# tms9918.net
KiCad netlist of a schematic drawn in EAGLE
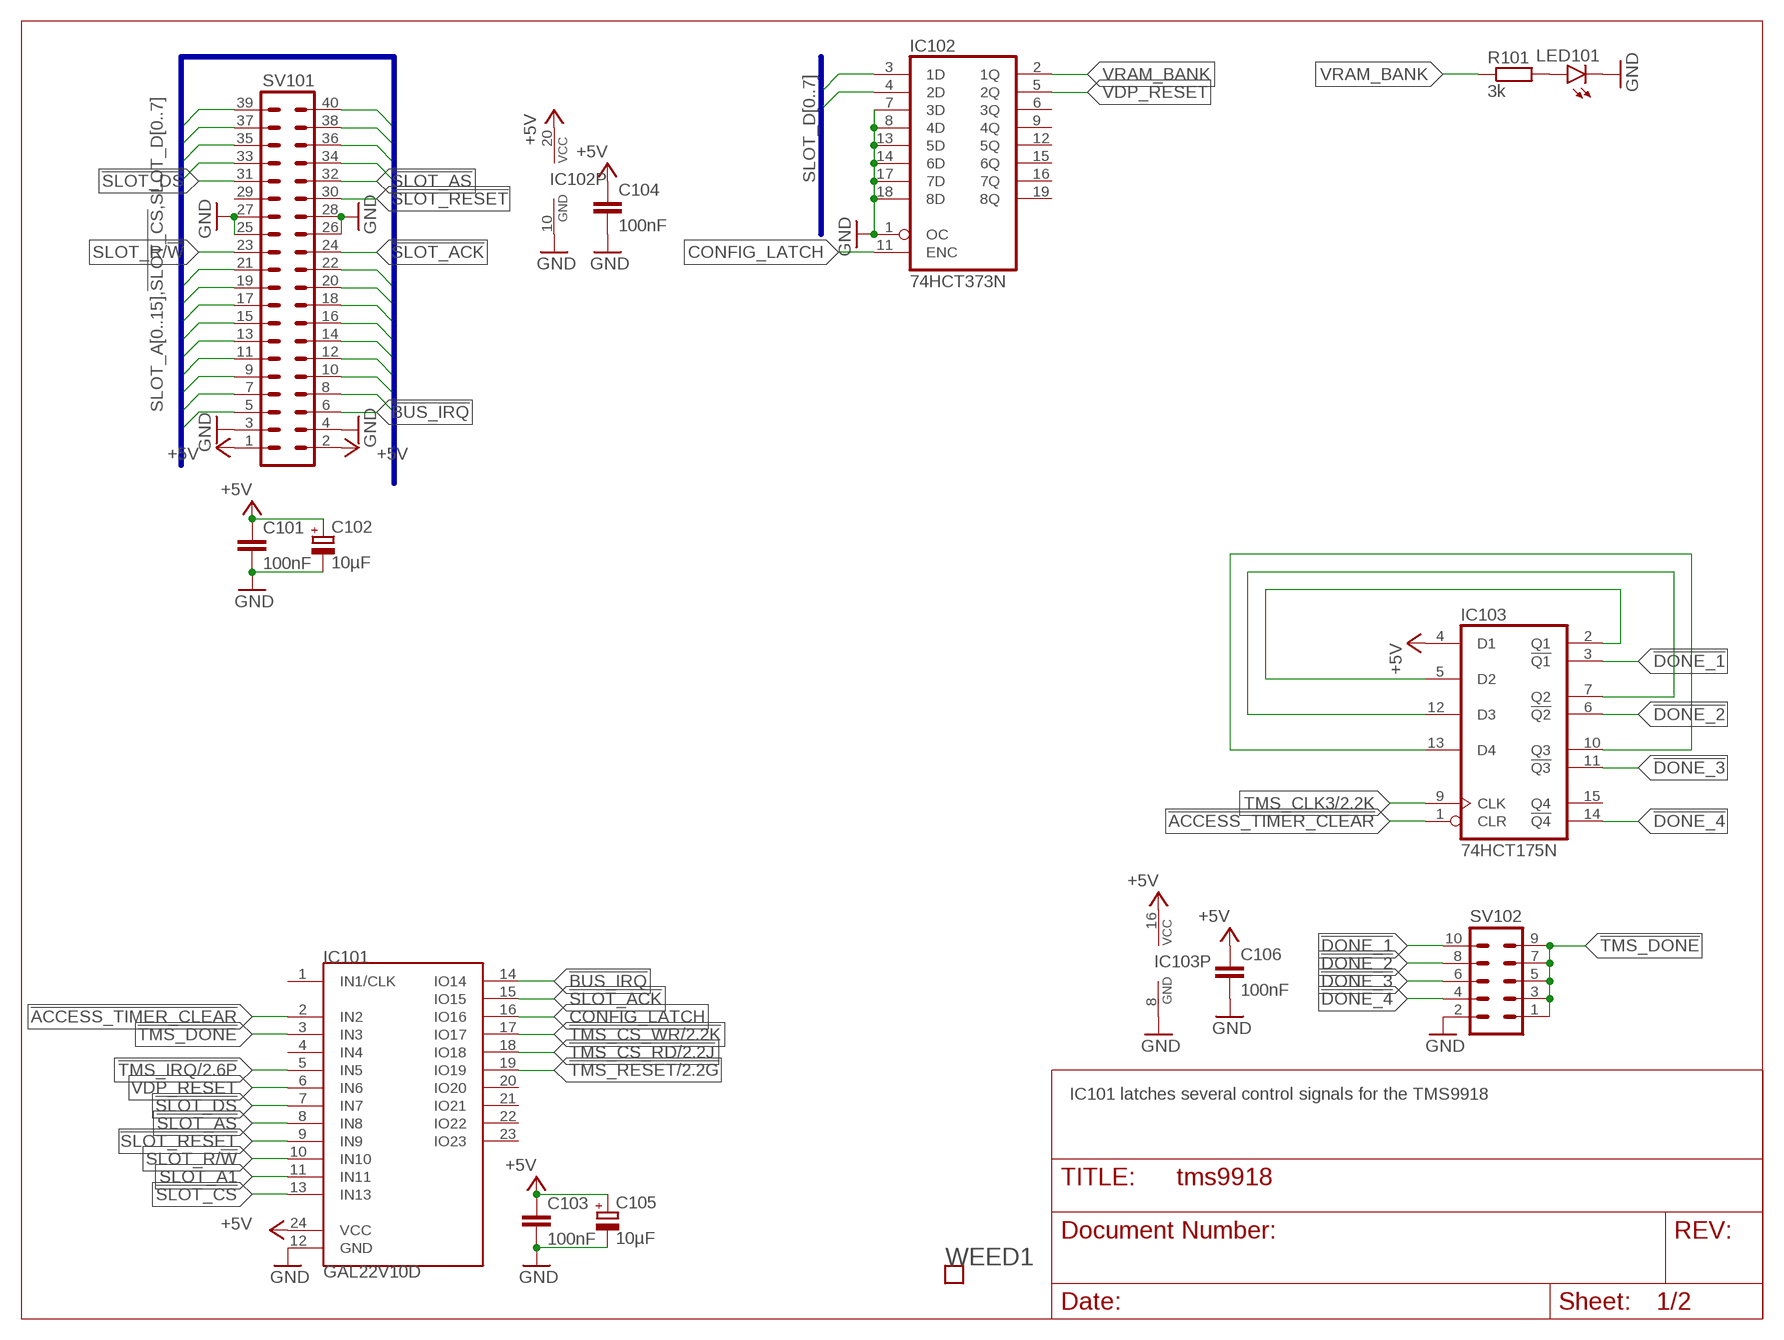
[diagram p0: schematic, sheet 1]
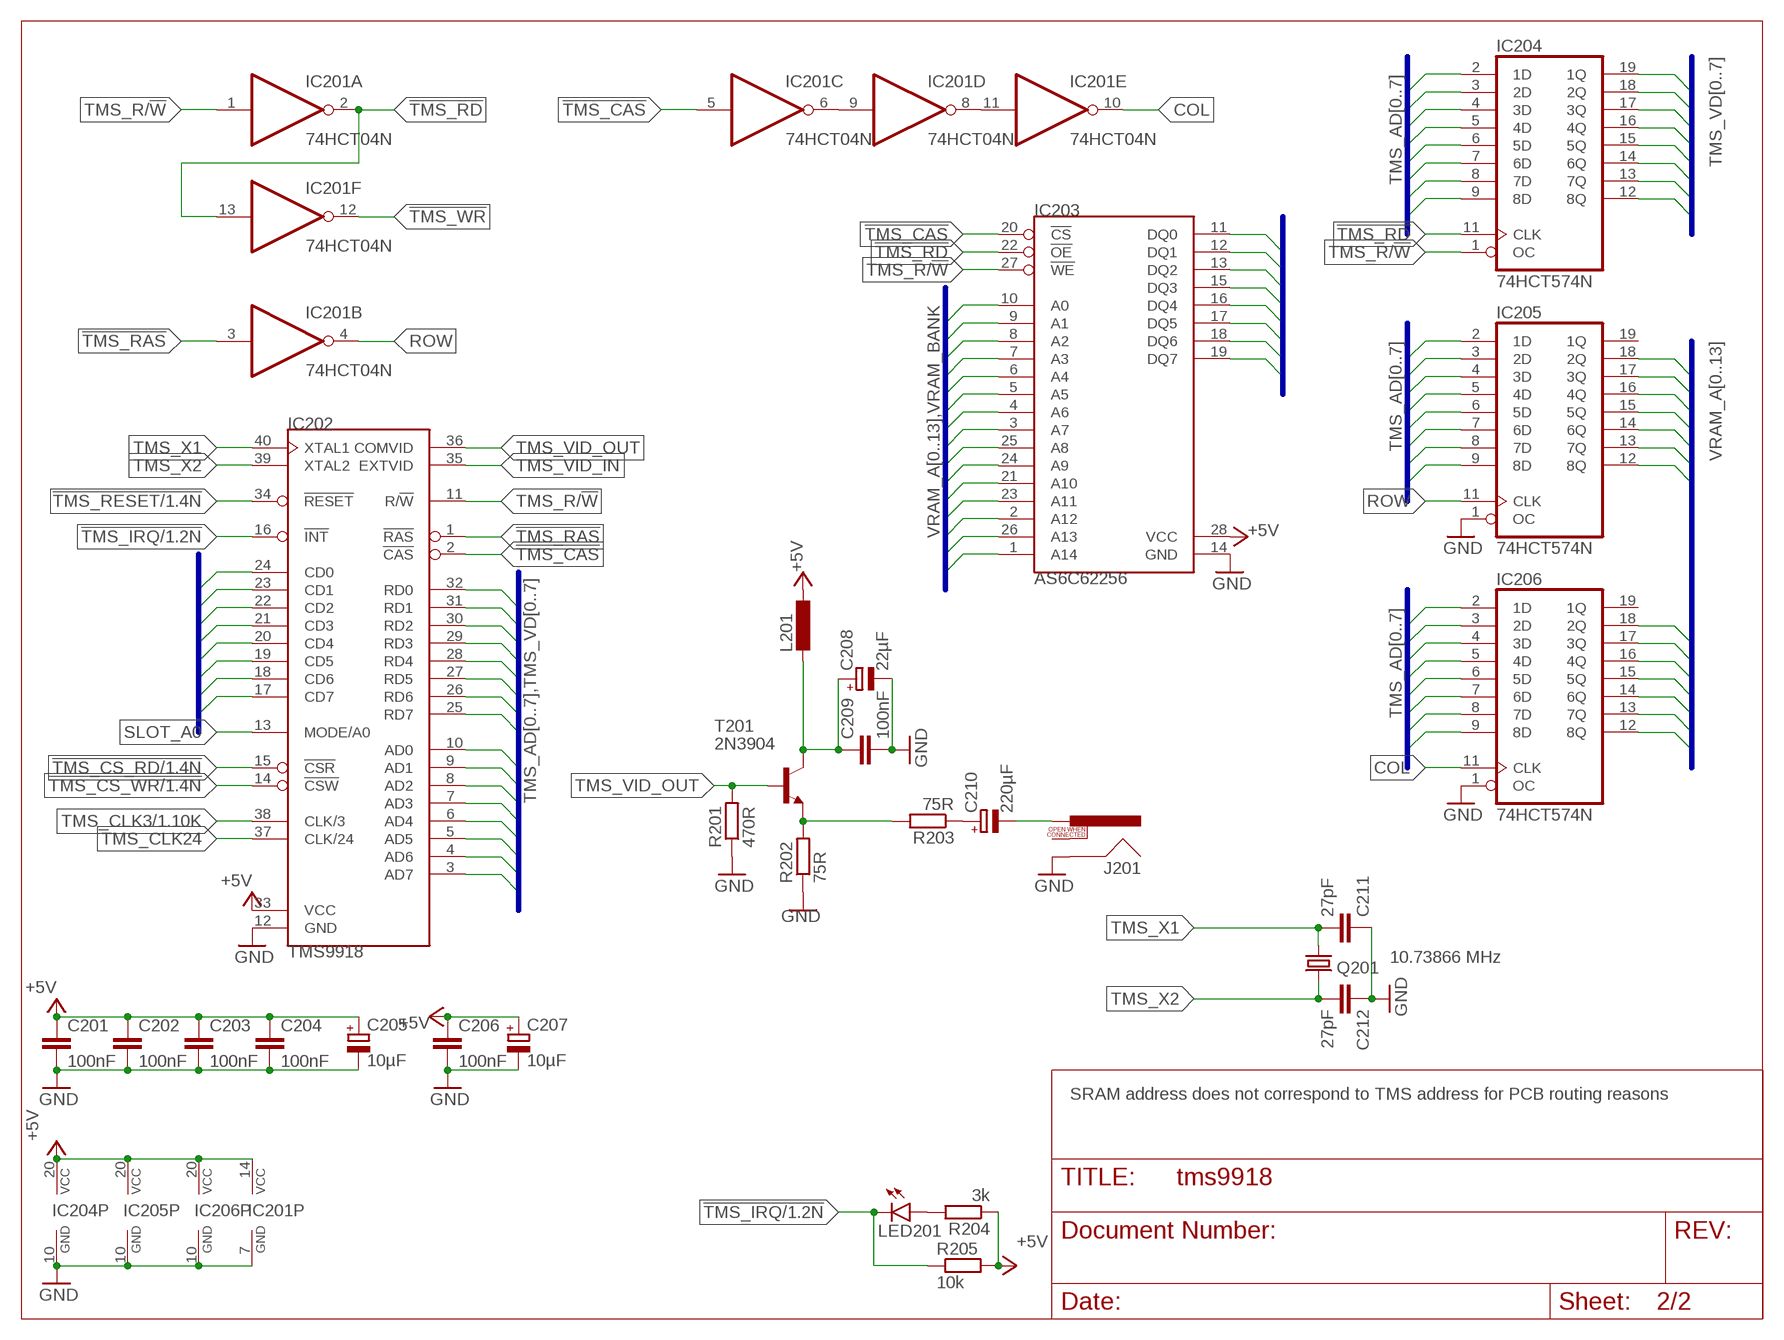
[diagram p1: schematic, sheet 2]

(export (version "E")
  (design (tool "Eeschema 10.0.6"))
  (components
    (comp (ref "C201")
      (value "100nF")
      (footprint "eagle-import:C0805")
      (libsource (lib "eagle-import") (part "C-EUC0805"))
    )
    (comp (ref "C202")
      (value "100nF")
      (footprint "eagle-import:C0805")
      (libsource (lib "eagle-import") (part "C-EUC0805"))
    )
    (comp (ref "C203")
      (value "100nF")
      (footprint "eagle-import:C0805")
      (libsource (lib "eagle-import") (part "C-EUC0805"))
    )
    (comp (ref "C204")
      (value "100nF")
      (footprint "eagle-import:C0805")
      (libsource (lib "eagle-import") (part "C-EUC0805"))
    )
    (comp (ref "C205")
      (value "10µF")
      (footprint "eagle-import:SMC_B")
      (libsource (lib "eagle-import") (part "CPOL-EUSMCB"))
    )
    (comp (ref "C206")
      (value "100nF")
      (footprint "eagle-import:C0805")
      (libsource (lib "eagle-import") (part "C-EUC0805"))
    )
    (comp (ref "C207")
      (value "10µF")
      (footprint "eagle-import:SMC_B")
      (libsource (lib "eagle-import") (part "CPOL-EUSMCB"))
    )
    (comp (ref "C208")
      (value "22µF")
      (footprint "eagle-import:E2-5")
      (libsource (lib "eagle-import") (part "CPOL-EUE2-5"))
    )
    (comp (ref "C209")
      (value "100nF")
      (footprint "eagle-import:C0805")
      (libsource (lib "eagle-import") (part "C-EUC0805"))
    )
    (comp (ref "C210")
      (value "220µF")
      (footprint "eagle-import:E2,5-7")
      (libsource (lib "eagle-import") (part "CPOL-EUE2.5-7"))
    )
    (comp (ref "C211")
      (value "27pF")
      (footprint "eagle-import:C0805")
      (libsource (lib "eagle-import") (part "C-EUC0805"))
    )
    (comp (ref "C212")
      (value "27pF")
      (footprint "eagle-import:C0805")
      (libsource (lib "eagle-import") (part "C-EUC0805"))
    )
    (comp (ref "IC201")
      (value "74HCT04N")
      (footprint "eagle-import:DIL14")
      (fields (field (name "MOUSER") "595-SN74HCT04N") (field (name "MOUSER_SOCKET") "575-1104731441001000"))
      (libsource (lib "eagle-import") (part "7404NHCT"))
    )
    (comp (ref "IC202")
      (value "TMS9918")
      (footprint "eagle-import:DIL40")
      (libsource (lib "eagle-import") (part "TMS9918"))
    )
    (comp (ref "IC203")
      (value "AS6C62256")
      (footprint "eagle-import:DIL28-6")
      (libsource (lib "eagle-import") (part "AS6C62256"))
    )
    (comp (ref "IC204")
      (value "74HCT574N")
      (footprint "eagle-import:DIL20")
      (fields (field (name "MOUSER") "595-SN74HCT574N") (field (name "MOUSER_SOCKET") "575-1104732041001000"))
      (libsource (lib "eagle-import") (part "74574NHCT"))
    )
    (comp (ref "IC205")
      (value "74HCT574N")
      (footprint "eagle-import:DIL20")
      (fields (field (name "MOUSER") "595-SN74HCT574N") (field (name "MOUSER_SOCKET") "575-1104732041001000"))
      (libsource (lib "eagle-import") (part "74574NHCT"))
    )
    (comp (ref "IC206")
      (value "74HCT574N")
      (footprint "eagle-import:DIL20")
      (fields (field (name "MOUSER") "595-SN74HCT574N") (field (name "MOUSER_SOCKET") "575-1104732041001000"))
      (libsource (lib "eagle-import") (part "74574NHCT"))
    )
    (comp (ref "J201")
      (value "RCALOCK")
      (footprint "eagle-import:RCA_LOCK")
      (libsource (lib "eagle-import") (part "RCALOCK"))
    )
    (comp (ref "L201")
      (value "L-EUL2012C")
      (footprint "eagle-import:L2012C")
      (libsource (lib "eagle-import") (part "L-EUL2012C"))
    )
    (comp (ref "LED201")
      (value "LEDCHIPLED_1206")
      (footprint "eagle-import:CHIPLED_1206")
      (libsource (lib "eagle-import") (part "LEDCHIPLED_1206"))
    )
    (comp (ref "Q201")
      (value "10.73866 MHz")
      (footprint "eagle-import:HC49_S")
      (libsource (lib "eagle-import") (part "CRYSTALHC49S"))
    )
    (comp (ref "R201")
      (value "470R")
      (footprint "eagle-import:R2012")
      (libsource (lib "eagle-import") (part "R-EU_R2012"))
    )
    (comp (ref "R202")
      (value "75R")
      (footprint "eagle-import:R2012")
      (libsource (lib "eagle-import") (part "R-EU_R2012"))
    )
    (comp (ref "R203")
      (value "75R")
      (footprint "eagle-import:R2012")
      (libsource (lib "eagle-import") (part "R-EU_R2012"))
    )
    (comp (ref "R204")
      (value "3k")
      (footprint "eagle-import:R2012")
      (libsource (lib "eagle-import") (part "R-EU_R2012"))
    )
    (comp (ref "R205")
      (value "10k")
      (footprint "eagle-import:R2012")
      (libsource (lib "eagle-import") (part "R-EU_R2012"))
    )
    (comp (ref "T201")
      (value "2N3904")
      (footprint "eagle-import:TO92")
      (libsource (lib "eagle-import") (part "2N3904"))
    )
    (comp (ref "C101")
      (value "100nF")
      (footprint "eagle-import:C0805")
      (libsource (lib "eagle-import") (part "C-EUC0805"))
    )
    (comp (ref "C102")
      (value "10µF")
      (footprint "eagle-import:SMC_B")
      (libsource (lib "eagle-import") (part "CPOL-EUSMCB"))
    )
    (comp (ref "C103")
      (value "100nF")
      (footprint "eagle-import:C0805")
      (libsource (lib "eagle-import") (part "C-EUC0805"))
    )
    (comp (ref "C104")
      (value "100nF")
      (footprint "eagle-import:C0805")
      (libsource (lib "eagle-import") (part "C-EUC0805"))
    )
    (comp (ref "C105")
      (value "10µF")
      (footprint "eagle-import:SMC_B")
      (libsource (lib "eagle-import") (part "CPOL-EUSMCB"))
    )
    (comp (ref "C106")
      (value "100nF")
      (footprint "eagle-import:C0805")
      (libsource (lib "eagle-import") (part "C-EUC0805"))
    )
    (comp (ref "IC101")
      (value "GAL22V10D")
      (footprint "eagle-import:DIL24S")
      (libsource (lib "eagle-import") (part "GAL22V10DIP24"))
    )
    (comp (ref "IC102")
      (value "74HCT373N")
      (footprint "eagle-import:DIL20")
      (fields (field (name "MOUSER") "595-SN74HCT373N") (field (name "MOUSER_SOCKET") "575-1104732041001000"))
      (libsource (lib "eagle-import") (part "74373NHCT"))
    )
    (comp (ref "IC103")
      (value "74HCT175N")
      (footprint "eagle-import:DIL16")
      (fields (field (name "MOUSER") "595-CD74HCT175E") (field (name "MOUSER_SOCKET") "575-1104731641001000"))
      (libsource (lib "eagle-import") (part "74175NHCT"))
    )
    (comp (ref "LED101")
      (value "LEDCHIPLED_1206")
      (footprint "eagle-import:CHIPLED_1206")
      (libsource (lib "eagle-import") (part "LEDCHIPLED_1206"))
    )
    (comp (ref "R101")
      (value "3k")
      (footprint "eagle-import:R2012")
      (libsource (lib "eagle-import") (part "R-EU_R2012"))
    )
    (comp (ref "SV101")
      (value "MA20-2W")
      (footprint "eagle-import:MA20-2W")
      (libsource (lib "eagle-import") (part "MA20-2W"))
    )
    (comp (ref "SV102")
      (value "MA05-2")
      (footprint "eagle-import:MA05-2")
      (libsource (lib "eagle-import") (part "MA05-2"))
    )
    (comp (ref "WEED1")
      (value "WEED")
      (footprint "eagle-import:DOINK")
      (libsource (lib "eagle-import") (part "WEED"))
    )
  )
  (nets
    (net (code "1") (name "+5V") (class "Default")
      (node (ref "C101") (pin "1") (pinfunction "1_1") (pintype "passive"))
      (node (ref "C102") (pin "+") (pinfunction "+_+") (pintype "passive"))
      (node (ref "C103") (pin "1") (pinfunction "1_1") (pintype "passive"))
      (node (ref "C104") (pin "1") (pinfunction "1_1") (pintype "passive"))
      (node (ref "C105") (pin "+") (pinfunction "+_+") (pintype "passive"))
      (node (ref "C106") (pin "1") (pinfunction "1_1") (pintype "passive"))
      (node (ref "C201") (pin "1") (pinfunction "1_1") (pintype "passive"))
      (node (ref "C202") (pin "1") (pinfunction "1_1") (pintype "passive"))
      (node (ref "C203") (pin "1") (pinfunction "1_1") (pintype "passive"))
      (node (ref "C204") (pin "1") (pinfunction "1_1") (pintype "passive"))
      (node (ref "C205") (pin "+") (pinfunction "+_+") (pintype "passive"))
      (node (ref "C206") (pin "1") (pinfunction "1_1") (pintype "passive"))
      (node (ref "C207") (pin "+") (pinfunction "+_+") (pintype "passive"))
      (node (ref "IC101") (pin "24") (pinfunction "VCC_24") (pintype "power_in"))
      (node (ref "IC102") (pin "20") (pinfunction "VCC_20") (pintype "power_in"))
      (node (ref "IC103") (pin "16") (pinfunction "VCC_16") (pintype "power_in"))
      (node (ref "IC103") (pin "4") (pinfunction "D1_4") (pintype "input"))
      (node (ref "IC201") (pin "14") (pinfunction "VCC_14") (pintype "power_in"))
      (node (ref "IC202") (pin "33") (pinfunction "VCC_33") (pintype "power_in"))
      (node (ref "IC203") (pin "28") (pinfunction "VCC_28") (pintype "power_in"))
      (node (ref "IC204") (pin "20") (pinfunction "VCC_20") (pintype "power_in"))
      (node (ref "IC205") (pin "20") (pinfunction "VCC_20") (pintype "power_in"))
      (node (ref "IC206") (pin "20") (pinfunction "VCC_20") (pintype "power_in"))
      (node (ref "L201") (pin "1") (pinfunction "1_1") (pintype "passive"))
      (node (ref "R204") (pin "1") (pinfunction "1_1") (pintype "passive"))
      (node (ref "R205") (pin "2") (pinfunction "2_2") (pintype "passive"))
      (node (ref "SV101") (pin "1") (pinfunction "1_1") (pintype "passive"))
      (node (ref "SV101") (pin "2") (pinfunction "2_2") (pintype "passive"))
    )
    (net (code "9") (name "COL") (class "Default")
      (node (ref "IC201") (pin "10") (pinfunction "O_10") (pintype "output"))
      (node (ref "IC206") (pin "11") (pinfunction "CLK_11") (pintype "input"))
    )
    (net (code "10") (name "CONFIG_LATCH") (class "Default")
      (node (ref "IC101") (pin "16") (pinfunction "IO16_16") (pintype "bidirectional"))
      (node (ref "IC102") (pin "11") (pinfunction "ENC_11") (pintype "input"))
    )
    (net (code "11") (name "GND") (class "Default")
      (node (ref "C101") (pin "2") (pinfunction "2_2") (pintype "passive"))
      (node (ref "C102") (pin "-") (pinfunction "-_-") (pintype "passive"))
      (node (ref "C103") (pin "2") (pinfunction "2_2") (pintype "passive"))
      (node (ref "C104") (pin "2") (pinfunction "2_2") (pintype "passive"))
      (node (ref "C105") (pin "-") (pinfunction "-_-") (pintype "passive"))
      (node (ref "C106") (pin "2") (pinfunction "2_2") (pintype "passive"))
      (node (ref "C201") (pin "2") (pinfunction "2_2") (pintype "passive"))
      (node (ref "C202") (pin "2") (pinfunction "2_2") (pintype "passive"))
      (node (ref "C203") (pin "2") (pinfunction "2_2") (pintype "passive"))
      (node (ref "C204") (pin "2") (pinfunction "2_2") (pintype "passive"))
      (node (ref "C205") (pin "-") (pinfunction "-_-") (pintype "passive"))
      (node (ref "C206") (pin "2") (pinfunction "2_2") (pintype "passive"))
      (node (ref "C207") (pin "-") (pinfunction "-_-") (pintype "passive"))
      (node (ref "C208") (pin "-") (pinfunction "-_-") (pintype "passive"))
      (node (ref "C209") (pin "2") (pinfunction "2_2") (pintype "passive"))
      (node (ref "C211") (pin "1") (pinfunction "1_1") (pintype "passive"))
      (node (ref "C212") (pin "1") (pinfunction "1_1") (pintype "passive"))
      (node (ref "IC101") (pin "12") (pinfunction "GND_12") (pintype "power_in"))
      (node (ref "IC102") (pin "1") (pinfunction "OC_1") (pintype "input"))
      (node (ref "IC102") (pin "10") (pinfunction "GND_10") (pintype "power_in"))
      (node (ref "IC102") (pin "13") (pinfunction "5D_13") (pintype "input"))
      (node (ref "IC102") (pin "14") (pinfunction "6D_14") (pintype "input"))
      (node (ref "IC102") (pin "17") (pinfunction "7D_17") (pintype "input"))
      (node (ref "IC102") (pin "18") (pinfunction "8D_18") (pintype "input"))
      (node (ref "IC102") (pin "7") (pinfunction "3D_7") (pintype "input"))
      (node (ref "IC102") (pin "8") (pinfunction "4D_8") (pintype "input"))
      (node (ref "IC103") (pin "8") (pinfunction "GND_8") (pintype "power_in"))
      (node (ref "IC201") (pin "7") (pinfunction "GND_7") (pintype "power_in"))
      (node (ref "IC202") (pin "12") (pinfunction "GND_12") (pintype "power_in"))
      (node (ref "IC203") (pin "14") (pinfunction "GND_14") (pintype "power_in"))
      (node (ref "IC204") (pin "10") (pinfunction "GND_10") (pintype "power_in"))
      (node (ref "IC205") (pin "1") (pinfunction "OC_1") (pintype "input"))
      (node (ref "IC205") (pin "10") (pinfunction "GND_10") (pintype "power_in"))
      (node (ref "IC206") (pin "1") (pinfunction "OC_1") (pintype "input"))
      (node (ref "IC206") (pin "10") (pinfunction "GND_10") (pintype "power_in"))
      (node (ref "J201") (pin "SHELL") (pinfunction "SHELL_SHELL") (pintype "bidirectional"))
      (node (ref "LED101") (pin "C") (pinfunction "C_C") (pintype "passive"))
      (node (ref "R201") (pin "1") (pinfunction "1_1") (pintype "passive"))
      (node (ref "R202") (pin "1") (pinfunction "1_1") (pintype "passive"))
      (node (ref "SV101") (pin "25") (pinfunction "25_25") (pintype "passive"))
      (node (ref "SV101") (pin "26") (pinfunction "26_26") (pintype "passive"))
      (node (ref "SV101") (pin "27") (pinfunction "27_27") (pintype "passive"))
      (node (ref "SV101") (pin "28") (pinfunction "28_28") (pintype "passive"))
      (node (ref "SV101") (pin "3") (pinfunction "3_3") (pintype "passive"))
      (node (ref "SV101") (pin "4") (pinfunction "4_4") (pintype "passive"))
      (node (ref "SV102") (pin "2") (pinfunction "2_2") (pintype "passive"))
    )
    (net (code "12") (name "Net-(C210-Pad+)") (class "Default")
      (node (ref "C210") (pin "+") (pinfunction "+_+") (pintype "passive"))
      (node (ref "R203") (pin "1") (pinfunction "1_1") (pintype "passive"))
    )
    (net (code "13") (name "Net-(C210-Pad-)") (class "Default")
      (node (ref "C210") (pin "-") (pinfunction "-_-") (pintype "passive"))
      (node (ref "J201") (pin "PIN") (pinfunction "PIN_PIN") (pintype "bidirectional"))
    )
    (net (code "14") (name "Net-(IC103A-D2)") (class "Default")
      (node (ref "IC103") (pin "2") (pinfunction "Q1_2") (pintype "output"))
      (node (ref "IC103") (pin "5") (pinfunction "D2_5") (pintype "input"))
    )
    (net (code "15") (name "Net-(IC103A-D3)") (class "Default")
      (node (ref "IC103") (pin "12") (pinfunction "D3_12") (pintype "input"))
      (node (ref "IC103") (pin "7") (pinfunction "Q2_7") (pintype "output"))
    )
    (net (code "16") (name "Net-(IC103A-D4)") (class "Default")
      (node (ref "IC103") (pin "10") (pinfunction "Q3_10") (pintype "output"))
      (node (ref "IC103") (pin "13") (pinfunction "D4_13") (pintype "input"))
    )
    (net (code "17") (name "Net-(IC201C-O)") (class "Default")
      (node (ref "IC201") (pin "6") (pinfunction "O_6") (pintype "output"))
      (node (ref "IC201") (pin "9") (pinfunction "I_9") (pintype "input"))
    )
    (net (code "18") (name "Net-(IC201D-O)") (class "Default")
      (node (ref "IC201") (pin "11") (pinfunction "I_11") (pintype "input"))
      (node (ref "IC201") (pin "8") (pinfunction "O_8") (pintype "output"))
    )
    (net (code "19") (name "Net-(LED101-PadA)") (class "Default")
      (node (ref "LED101") (pin "A") (pinfunction "A_A") (pintype "passive"))
      (node (ref "R101") (pin "2") (pinfunction "2_2") (pintype "passive"))
    )
    (net (code "20") (name "Net-(LED201-PadA)") (class "Default")
      (node (ref "LED201") (pin "A") (pinfunction "A_A") (pintype "passive"))
      (node (ref "R204") (pin "2") (pinfunction "2_2") (pintype "passive"))
    )
    (net (code "21") (name "Net-(T201-C)") (class "Default")
      (node (ref "C208") (pin "+") (pinfunction "+_+") (pintype "passive"))
      (node (ref "C209") (pin "1") (pinfunction "1_1") (pintype "passive"))
      (node (ref "L201") (pin "2") (pinfunction "2_2") (pintype "passive"))
      (node (ref "T201") (pin "1") (pinfunction "C_1") (pintype "passive"))
    )
    (net (code "22") (name "Net-(T201-E)") (class "Default")
      (node (ref "R202") (pin "2") (pinfunction "2_2") (pintype "passive"))
      (node (ref "R203") (pin "2") (pinfunction "2_2") (pintype "passive"))
      (node (ref "T201") (pin "3") (pinfunction "E_3") (pintype "passive"))
    )
    (net (code "23") (name "ROW") (class "Default")
      (node (ref "IC201") (pin "4") (pinfunction "O_4") (pintype "output"))
      (node (ref "IC205") (pin "11") (pinfunction "CLK_11") (pintype "input"))
    )
    (net (code "24") (name "SLOT_A0") (class "Default")
      (node (ref "IC202") (pin "13") (pinfunction "MODE/A0_13") (pintype "input"))
      (node (ref "SV101") (pin "12") (pinfunction "12_12") (pintype "passive"))
    )
    (net (code "25") (name "SLOT_A1") (class "Default")
      (node (ref "IC101") (pin "11") (pinfunction "IN11_11") (pintype "input"))
      (node (ref "SV101") (pin "10") (pinfunction "10_10") (pintype "passive"))
    )
    (net (code "26") (name "SLOT_D0") (class "Default")
      (node (ref "IC102") (pin "3") (pinfunction "1D_3") (pintype "input"))
      (node (ref "IC202") (pin "17") (pinfunction "CD7_17") (pintype "bidirectional"))
      (node (ref "SV101") (pin "35") (pinfunction "35_35") (pintype "passive"))
    )
    (net (code "27") (name "SLOT_D1") (class "Default")
      (node (ref "IC102") (pin "4") (pinfunction "2D_4") (pintype "input"))
      (node (ref "IC202") (pin "18") (pinfunction "CD6_18") (pintype "bidirectional"))
      (node (ref "SV101") (pin "37") (pinfunction "37_37") (pintype "passive"))
    )
    (net (code "28") (name "SLOT_D2") (class "Default")
      (node (ref "IC202") (pin "19") (pinfunction "CD5_19") (pintype "bidirectional"))
      (node (ref "SV101") (pin "39") (pinfunction "39_39") (pintype "passive"))
    )
    (net (code "29") (name "SLOT_D3") (class "Default")
      (node (ref "IC202") (pin "20") (pinfunction "CD4_20") (pintype "bidirectional"))
      (node (ref "SV101") (pin "40") (pinfunction "40_40") (pintype "passive"))
    )
    (net (code "30") (name "SLOT_D4") (class "Default")
      (node (ref "IC202") (pin "21") (pinfunction "CD3_21") (pintype "bidirectional"))
      (node (ref "SV101") (pin "38") (pinfunction "38_38") (pintype "passive"))
    )
    (net (code "31") (name "SLOT_D5") (class "Default")
      (node (ref "IC202") (pin "22") (pinfunction "CD2_22") (pintype "bidirectional"))
      (node (ref "SV101") (pin "36") (pinfunction "36_36") (pintype "passive"))
    )
    (net (code "32") (name "SLOT_D6") (class "Default")
      (node (ref "IC202") (pin "23") (pinfunction "CD1_23") (pintype "bidirectional"))
      (node (ref "SV101") (pin "34") (pinfunction "34_34") (pintype "passive"))
    )
    (net (code "33") (name "SLOT_D7") (class "Default")
      (node (ref "IC202") (pin "24") (pinfunction "CD0_24") (pintype "bidirectional"))
      (node (ref "SV101") (pin "33") (pinfunction "33_33") (pintype "passive"))
    )
    (net (code "34") (name "SLOT_R{slash}~{W}") (class "Default")
      (node (ref "IC101") (pin "10") (pinfunction "IN10_10") (pintype "input"))
      (node (ref "SV101") (pin "23") (pinfunction "23_23") (pintype "passive"))
    )
    (net (code "35") (name "TMS_AD0") (class "Default")
      (node (ref "IC202") (pin "10") (pinfunction "AD0_10") (pintype "input"))
      (node (ref "IC204") (pin "2") (pinfunction "1D_2") (pintype "input"))
      (node (ref "IC205") (pin "9") (pinfunction "8D_9") (pintype "input"))
      (node (ref "IC206") (pin "9") (pinfunction "8D_9") (pintype "input"))
    )
    (net (code "36") (name "TMS_AD1") (class "Default")
      (node (ref "IC202") (pin "9") (pinfunction "AD1_9") (pintype "input"))
      (node (ref "IC204") (pin "3") (pinfunction "2D_3") (pintype "input"))
      (node (ref "IC205") (pin "8") (pinfunction "7D_8") (pintype "input"))
      (node (ref "IC206") (pin "8") (pinfunction "7D_8") (pintype "input"))
    )
    (net (code "37") (name "TMS_AD2") (class "Default")
      (node (ref "IC202") (pin "8") (pinfunction "AD2_8") (pintype "input"))
      (node (ref "IC204") (pin "4") (pinfunction "3D_4") (pintype "input"))
      (node (ref "IC205") (pin "7") (pinfunction "6D_7") (pintype "input"))
      (node (ref "IC206") (pin "7") (pinfunction "6D_7") (pintype "input"))
    )
    (net (code "38") (name "TMS_AD3") (class "Default")
      (node (ref "IC202") (pin "7") (pinfunction "AD3_7") (pintype "input"))
      (node (ref "IC204") (pin "5") (pinfunction "4D_5") (pintype "input"))
      (node (ref "IC205") (pin "6") (pinfunction "5D_6") (pintype "input"))
      (node (ref "IC206") (pin "6") (pinfunction "5D_6") (pintype "input"))
    )
    (net (code "39") (name "TMS_AD4") (class "Default")
      (node (ref "IC202") (pin "6") (pinfunction "AD4_6") (pintype "input"))
      (node (ref "IC204") (pin "6") (pinfunction "5D_6") (pintype "input"))
      (node (ref "IC205") (pin "5") (pinfunction "4D_5") (pintype "input"))
      (node (ref "IC206") (pin "5") (pinfunction "4D_5") (pintype "input"))
    )
    (net (code "40") (name "TMS_AD5") (class "Default")
      (node (ref "IC202") (pin "5") (pinfunction "AD5_5") (pintype "input"))
      (node (ref "IC204") (pin "7") (pinfunction "6D_7") (pintype "input"))
      (node (ref "IC205") (pin "4") (pinfunction "3D_4") (pintype "input"))
      (node (ref "IC206") (pin "4") (pinfunction "3D_4") (pintype "input"))
    )
    (net (code "41") (name "TMS_AD6") (class "Default")
      (node (ref "IC202") (pin "4") (pinfunction "AD6_4") (pintype "input"))
      (node (ref "IC204") (pin "8") (pinfunction "7D_8") (pintype "input"))
      (node (ref "IC205") (pin "3") (pinfunction "2D_3") (pintype "input"))
      (node (ref "IC206") (pin "3") (pinfunction "2D_3") (pintype "input"))
    )
    (net (code "42") (name "TMS_AD7") (class "Default")
      (node (ref "IC202") (pin "3") (pinfunction "AD7_3") (pintype "input"))
      (node (ref "IC204") (pin "9") (pinfunction "8D_9") (pintype "input"))
      (node (ref "IC205") (pin "2") (pinfunction "1D_2") (pintype "input"))
      (node (ref "IC206") (pin "2") (pinfunction "1D_2") (pintype "input"))
    )
    (net (code "43") (name "TMS_CLK3") (class "Default")
      (node (ref "IC103") (pin "9") (pinfunction "CLK_9") (pintype "input"))
      (node (ref "IC202") (pin "38") (pinfunction "CLK/3_38") (pintype "output"))
    )
    (net (code "44") (name "TMS_CLK24") (class "Default")
      (node (ref "IC202") (pin "37") (pinfunction "CLK/24_37") (pintype "output"))
    )
    (net (code "45") (name "TMS_R{slash}~{W}") (class "Default")
      (node (ref "IC201") (pin "1") (pinfunction "I_1") (pintype "input"))
      (node (ref "IC202") (pin "11") (pinfunction "R/~{W}_11") (pintype "output"))
      (node (ref "IC203") (pin "27") (pinfunction "~{WE}_27") (pintype "input"))
      (node (ref "IC204") (pin "1") (pinfunction "OC_1") (pintype "input"))
    )
    (net (code "46") (name "TMS_VD0") (class "Default")
      (node (ref "IC202") (pin "32") (pinfunction "RD0_32") (pintype "input"))
      (node (ref "IC203") (pin "11") (pinfunction "DQ0_11") (pintype "bidirectional"))
      (node (ref "IC204") (pin "19") (pinfunction "1Q_19") (pintype "tri_state"))
    )
    (net (code "47") (name "TMS_VD1") (class "Default")
      (node (ref "IC202") (pin "31") (pinfunction "RD1_31") (pintype "input"))
      (node (ref "IC203") (pin "12") (pinfunction "DQ1_12") (pintype "bidirectional"))
      (node (ref "IC204") (pin "18") (pinfunction "2Q_18") (pintype "tri_state"))
    )
    (net (code "48") (name "TMS_VD2") (class "Default")
      (node (ref "IC202") (pin "30") (pinfunction "RD2_30") (pintype "input"))
      (node (ref "IC203") (pin "13") (pinfunction "DQ2_13") (pintype "bidirectional"))
      (node (ref "IC204") (pin "17") (pinfunction "3Q_17") (pintype "tri_state"))
    )
    (net (code "49") (name "TMS_VD3") (class "Default")
      (node (ref "IC202") (pin "29") (pinfunction "RD3_29") (pintype "input"))
      (node (ref "IC203") (pin "15") (pinfunction "DQ3_15") (pintype "bidirectional"))
      (node (ref "IC204") (pin "16") (pinfunction "4Q_16") (pintype "tri_state"))
    )
    (net (code "50") (name "TMS_VD4") (class "Default")
      (node (ref "IC202") (pin "28") (pinfunction "RD4_28") (pintype "input"))
      (node (ref "IC203") (pin "16") (pinfunction "DQ4_16") (pintype "bidirectional"))
      (node (ref "IC204") (pin "15") (pinfunction "5Q_15") (pintype "tri_state"))
    )
    (net (code "51") (name "TMS_VD5") (class "Default")
      (node (ref "IC202") (pin "27") (pinfunction "RD5_27") (pintype "input"))
      (node (ref "IC203") (pin "17") (pinfunction "DQ5_17") (pintype "bidirectional"))
      (node (ref "IC204") (pin "14") (pinfunction "6Q_14") (pintype "tri_state"))
    )
    (net (code "52") (name "TMS_VD6") (class "Default")
      (node (ref "IC202") (pin "26") (pinfunction "RD6_26") (pintype "input"))
      (node (ref "IC203") (pin "18") (pinfunction "DQ6_18") (pintype "bidirectional"))
      (node (ref "IC204") (pin "13") (pinfunction "7Q_13") (pintype "tri_state"))
    )
    (net (code "53") (name "TMS_VD7") (class "Default")
      (node (ref "IC202") (pin "25") (pinfunction "RD7_25") (pintype "input"))
      (node (ref "IC203") (pin "19") (pinfunction "DQ7_19") (pintype "bidirectional"))
      (node (ref "IC204") (pin "12") (pinfunction "8Q_12") (pintype "tri_state"))
    )
    (net (code "54") (name "TMS_VID_IN") (class "Default")
      (node (ref "IC202") (pin "35") (pinfunction "EXTVID_35") (pintype "input"))
    )
    (net (code "55") (name "TMS_VID_OUT") (class "Default")
      (node (ref "IC202") (pin "36") (pinfunction "COMVID_36") (pintype "output"))
      (node (ref "R201") (pin "2") (pinfunction "2_2") (pintype "passive"))
      (node (ref "T201") (pin "2") (pinfunction "B_2") (pintype "passive"))
    )
    (net (code "56") (name "TMS_X1") (class "Default")
      (node (ref "C211") (pin "2") (pinfunction "2_2") (pintype "passive"))
      (node (ref "IC202") (pin "40") (pinfunction "XTAL1_40") (pintype "passive"))
      (node (ref "Q201") (pin "1") (pinfunction "1_1") (pintype "passive"))
    )
    (net (code "57") (name "TMS_X2") (class "Default")
      (node (ref "C212") (pin "2") (pinfunction "2_2") (pintype "passive"))
      (node (ref "IC202") (pin "39") (pinfunction "XTAL2_39") (pintype "passive"))
      (node (ref "Q201") (pin "2") (pinfunction "2_2") (pintype "passive"))
    )
    (net (code "58") (name "VDP_RESET") (class "Default")
      (node (ref "IC101") (pin "6") (pinfunction "IN6_6") (pintype "input"))
      (node (ref "IC102") (pin "5") (pinfunction "2Q_5") (pintype "tri_state"))
    )
    (net (code "59") (name "VRAM_A0") (class "Default")
      (node (ref "IC203") (pin "10") (pinfunction "A0_10") (pintype "input"))
      (node (ref "IC205") (pin "12") (pinfunction "8Q_12") (pintype "tri_state"))
    )
    (net (code "60") (name "VRAM_A1") (class "Default")
      (node (ref "IC203") (pin "9") (pinfunction "A1_9") (pintype "input"))
      (node (ref "IC205") (pin "13") (pinfunction "7Q_13") (pintype "tri_state"))
    )
    (net (code "61") (name "VRAM_A2") (class "Default")
      (node (ref "IC203") (pin "8") (pinfunction "A2_8") (pintype "input"))
      (node (ref "IC205") (pin "14") (pinfunction "6Q_14") (pintype "tri_state"))
    )
    (net (code "62") (name "VRAM_A3") (class "Default")
      (node (ref "IC203") (pin "7") (pinfunction "A3_7") (pintype "input"))
      (node (ref "IC205") (pin "15") (pinfunction "5Q_15") (pintype "tri_state"))
    )
    (net (code "63") (name "VRAM_A4") (class "Default")
      (node (ref "IC203") (pin "6") (pinfunction "A4_6") (pintype "input"))
      (node (ref "IC205") (pin "16") (pinfunction "4Q_16") (pintype "tri_state"))
    )
    (net (code "64") (name "VRAM_A5") (class "Default")
      (node (ref "IC203") (pin "5") (pinfunction "A5_5") (pintype "input"))
      (node (ref "IC205") (pin "17") (pinfunction "3Q_17") (pintype "tri_state"))
    )
    (net (code "65") (name "VRAM_A6") (class "Default")
      (node (ref "IC203") (pin "4") (pinfunction "A6_4") (pintype "input"))
      (node (ref "IC205") (pin "18") (pinfunction "2Q_18") (pintype "tri_state"))
    )
    (net (code "66") (name "VRAM_A7") (class "Default")
      (node (ref "IC203") (pin "3") (pinfunction "A7_3") (pintype "input"))
      (node (ref "IC206") (pin "17") (pinfunction "3Q_17") (pintype "tri_state"))
    )
    (net (code "67") (name "VRAM_A8") (class "Default")
      (node (ref "IC203") (pin "25") (pinfunction "A8_25") (pintype "input"))
      (node (ref "IC206") (pin "15") (pinfunction "5Q_15") (pintype "tri_state"))
    )
    (net (code "68") (name "VRAM_A9") (class "Default")
      (node (ref "IC203") (pin "24") (pinfunction "A9_24") (pintype "input"))
      (node (ref "IC206") (pin "14") (pinfunction "6Q_14") (pintype "tri_state"))
    )
    (net (code "69") (name "VRAM_A10") (class "Default")
      (node (ref "IC203") (pin "21") (pinfunction "A10_21") (pintype "input"))
      (node (ref "IC206") (pin "12") (pinfunction "8Q_12") (pintype "tri_state"))
    )
    (net (code "70") (name "VRAM_A11") (class "Default")
      (node (ref "IC203") (pin "23") (pinfunction "A11_23") (pintype "input"))
      (node (ref "IC206") (pin "13") (pinfunction "7Q_13") (pintype "tri_state"))
    )
    (net (code "71") (name "VRAM_A12") (class "Default")
      (node (ref "IC203") (pin "2") (pinfunction "A12_2") (pintype "input"))
      (node (ref "IC206") (pin "18") (pinfunction "2Q_18") (pintype "tri_state"))
    )
    (net (code "72") (name "VRAM_A13") (class "Default")
      (node (ref "IC203") (pin "26") (pinfunction "A13_26") (pintype "input"))
      (node (ref "IC206") (pin "16") (pinfunction "4Q_16") (pintype "tri_state"))
    )
    (net (code "73") (name "VRAM_BANK") (class "Default")
      (node (ref "IC102") (pin "2") (pinfunction "1Q_2") (pintype "tri_state"))
      (node (ref "IC203") (pin "1") (pinfunction "A14_1") (pintype "input"))
      (node (ref "R101") (pin "1") (pinfunction "1_1") (pintype "passive"))
    )
    (net (code "74") (name "unconnected-(IC101-IN1{slash}CLK-Pad1)") (class "Default")
      (node (ref "IC101") (pin "1") (pinfunction "IN1/CLK_1") (pintype "input"))
    )
    (net (code "75") (name "unconnected-(IC101-IN4-Pad4)") (class "Default")
      (node (ref "IC101") (pin "4") (pinfunction "IN4_4") (pintype "input"))
    )
    (net (code "76") (name "unconnected-(IC101-IO20-Pad20)") (class "Default")
      (node (ref "IC101") (pin "20") (pinfunction "IO20_20") (pintype "bidirectional"))
    )
    (net (code "77") (name "unconnected-(IC101-IO21-Pad21)") (class "Default")
      (node (ref "IC101") (pin "21") (pinfunction "IO21_21") (pintype "bidirectional"))
    )
    (net (code "78") (name "unconnected-(IC101-IO22-Pad22)") (class "Default")
      (node (ref "IC101") (pin "22") (pinfunction "IO22_22") (pintype "bidirectional"))
    )
    (net (code "79") (name "unconnected-(IC101-IO23-Pad23)") (class "Default")
      (node (ref "IC101") (pin "23") (pinfunction "IO23_23") (pintype "bidirectional"))
    )
    (net (code "80") (name "unconnected-(IC102A-3Q-Pad6)") (class "Default")
      (node (ref "IC102") (pin "6") (pinfunction "3Q_6") (pintype "tri_state"))
    )
    (net (code "81") (name "unconnected-(IC102A-4Q-Pad9)") (class "Default")
      (node (ref "IC102") (pin "9") (pinfunction "4Q_9") (pintype "tri_state"))
    )
    (net (code "82") (name "unconnected-(IC102A-5Q-Pad12)") (class "Default")
      (node (ref "IC102") (pin "12") (pinfunction "5Q_12") (pintype "tri_state"))
    )
    (net (code "83") (name "unconnected-(IC102A-6Q-Pad15)") (class "Default")
      (node (ref "IC102") (pin "15") (pinfunction "6Q_15") (pintype "tri_state"))
    )
    (net (code "84") (name "unconnected-(IC102A-7Q-Pad16)") (class "Default")
      (node (ref "IC102") (pin "16") (pinfunction "7Q_16") (pintype "tri_state"))
    )
    (net (code "85") (name "unconnected-(IC102A-8Q-Pad19)") (class "Default")
      (node (ref "IC102") (pin "19") (pinfunction "8Q_19") (pintype "tri_state"))
    )
    (net (code "86") (name "unconnected-(IC103A-Q4-Pad15)") (class "Default")
      (node (ref "IC103") (pin "15") (pinfunction "Q4_15") (pintype "output"))
    )
    (net (code "87") (name "unconnected-(IC205A-1Q-Pad19)") (class "Default")
      (node (ref "IC205") (pin "19") (pinfunction "1Q_19") (pintype "tri_state"))
    )
    (net (code "88") (name "unconnected-(IC206A-1Q-Pad19)") (class "Default")
      (node (ref "IC206") (pin "19") (pinfunction "1Q_19") (pintype "tri_state"))
    )
    (net (code "89") (name "unconnected-(J201-PadSWITCH)") (class "Default")
      (node (ref "J201") (pin "SWITCH") (pinfunction "SWITCH_SWITCH") (pintype "bidirectional"))
    )
    (net (code "90") (name "unconnected-(SV101-Pad7)") (class "Default")
      (node (ref "SV101") (pin "7") (pinfunction "7_7") (pintype "passive"))
    )
    (net (code "91") (name "unconnected-(SV101-Pad8)") (class "Default")
      (node (ref "SV101") (pin "8") (pinfunction "8_8") (pintype "passive"))
    )
    (net (code "92") (name "unconnected-(SV101-Pad9)") (class "Default")
      (node (ref "SV101") (pin "9") (pinfunction "9_9") (pintype "passive"))
    )
    (net (code "93") (name "unconnected-(SV101-Pad11)") (class "Default")
      (node (ref "SV101") (pin "11") (pinfunction "11_11") (pintype "passive"))
    )
    (net (code "94") (name "unconnected-(SV101-Pad13)") (class "Default")
      (node (ref "SV101") (pin "13") (pinfunction "13_13") (pintype "passive"))
    )
    (net (code "95") (name "unconnected-(SV101-Pad14)") (class "Default")
      (node (ref "SV101") (pin "14") (pinfunction "14_14") (pintype "passive"))
    )
    (net (code "96") (name "unconnected-(SV101-Pad15)") (class "Default")
      (node (ref "SV101") (pin "15") (pinfunction "15_15") (pintype "passive"))
    )
    (net (code "97") (name "unconnected-(SV101-Pad16)") (class "Default")
      (node (ref "SV101") (pin "16") (pinfunction "16_16") (pintype "passive"))
    )
    (net (code "98") (name "unconnected-(SV101-Pad17)") (class "Default")
      (node (ref "SV101") (pin "17") (pinfunction "17_17") (pintype "passive"))
    )
    (net (code "99") (name "unconnected-(SV101-Pad18)") (class "Default")
      (node (ref "SV101") (pin "18") (pinfunction "18_18") (pintype "passive"))
    )
    (net (code "100") (name "unconnected-(SV101-Pad19)") (class "Default")
      (node (ref "SV101") (pin "19") (pinfunction "19_19") (pintype "passive"))
    )
    (net (code "101") (name "unconnected-(SV101-Pad20)") (class "Default")
      (node (ref "SV101") (pin "20") (pinfunction "20_20") (pintype "passive"))
    )
    (net (code "102") (name "unconnected-(SV101-Pad21)") (class "Default")
      (node (ref "SV101") (pin "21") (pinfunction "21_21") (pintype "passive"))
    )
    (net (code "103") (name "unconnected-(SV101-Pad22)") (class "Default")
      (node (ref "SV101") (pin "22") (pinfunction "22_22") (pintype "passive"))
    )
    (net (code "104") (name "unconnected-(SV101-Pad29)") (class "Default")
      (node (ref "SV101") (pin "29") (pinfunction "29_29") (pintype "passive"))
    )
    (net (code "105") (name "~{ACCESS_TIMER_CLEAR}") (class "Default")
      (node (ref "IC101") (pin "2") (pinfunction "IN2_2") (pintype "input"))
      (node (ref "IC103") (pin "1") (pinfunction "CLR_1") (pintype "input"))
    )
    (net (code "106") (name "~{BUS_IRQ}") (class "Default")
      (node (ref "IC101") (pin "14") (pinfunction "IO14_14") (pintype "bidirectional"))
      (node (ref "SV101") (pin "6") (pinfunction "6_6") (pintype "passive"))
    )
    (net (code "107") (name "~{DONE_1}") (class "Default")
      (node (ref "IC103") (pin "3") (pinfunction "~{Q1}_3") (pintype "output"))
      (node (ref "SV102") (pin "10") (pinfunction "10_10") (pintype "passive"))
    )
    (net (code "108") (name "~{DONE_2}") (class "Default")
      (node (ref "IC103") (pin "6") (pinfunction "~{Q2}_6") (pintype "output"))
      (node (ref "SV102") (pin "8") (pinfunction "8_8") (pintype "passive"))
    )
    (net (code "109") (name "~{DONE_3}") (class "Default")
      (node (ref "IC103") (pin "11") (pinfunction "~{Q3}_11") (pintype "output"))
      (node (ref "SV102") (pin "6") (pinfunction "6_6") (pintype "passive"))
    )
    (net (code "110") (name "~{DONE_4}") (class "Default")
      (node (ref "IC103") (pin "14") (pinfunction "~{Q4}_14") (pintype "output"))
      (node (ref "SV102") (pin "4") (pinfunction "4_4") (pintype "passive"))
    )
    (net (code "111") (name "~{SLOT_ACK}") (class "Default")
      (node (ref "IC101") (pin "15") (pinfunction "IO15_15") (pintype "bidirectional"))
      (node (ref "SV101") (pin "24") (pinfunction "24_24") (pintype "passive"))
    )
    (net (code "112") (name "~{SLOT_AS}") (class "Default")
      (node (ref "IC101") (pin "8") (pinfunction "IN8_8") (pintype "input"))
      (node (ref "SV101") (pin "32") (pinfunction "32_32") (pintype "passive"))
    )
    (net (code "113") (name "~{SLOT_CS}") (class "Default")
      (node (ref "IC101") (pin "13") (pinfunction "IN13_13") (pintype "input"))
      (node (ref "SV101") (pin "5") (pinfunction "5_5") (pintype "passive"))
    )
    (net (code "114") (name "~{SLOT_DS}") (class "Default")
      (node (ref "IC101") (pin "7") (pinfunction "IN7_7") (pintype "input"))
      (node (ref "SV101") (pin "31") (pinfunction "31_31") (pintype "passive"))
    )
    (net (code "115") (name "~{SLOT_RESET}") (class "Default")
      (node (ref "IC101") (pin "9") (pinfunction "IN9_9") (pintype "input"))
      (node (ref "SV101") (pin "30") (pinfunction "30_30") (pintype "passive"))
    )
    (net (code "116") (name "~{TMS_CAS}") (class "Default")
      (node (ref "IC201") (pin "5") (pinfunction "I_5") (pintype "input"))
      (node (ref "IC202") (pin "2") (pinfunction "~{CAS}_2") (pintype "output"))
      (node (ref "IC203") (pin "20") (pinfunction "~{CS}_20") (pintype "input"))
    )
    (net (code "117") (name "~{TMS_CS_RD}") (class "Default")
      (node (ref "IC101") (pin "18") (pinfunction "IO18_18") (pintype "bidirectional"))
      (node (ref "IC202") (pin "15") (pinfunction "~{CSR}_15") (pintype "input"))
    )
    (net (code "118") (name "~{TMS_CS_WR}") (class "Default")
      (node (ref "IC101") (pin "17") (pinfunction "IO17_17") (pintype "bidirectional"))
      (node (ref "IC202") (pin "14") (pinfunction "~{CSW}_14") (pintype "input"))
    )
    (net (code "119") (name "~{TMS_DONE}") (class "Default")
      (node (ref "IC101") (pin "3") (pinfunction "IN3_3") (pintype "input"))
      (node (ref "SV102") (pin "1") (pinfunction "1_1") (pintype "passive"))
      (node (ref "SV102") (pin "3") (pinfunction "3_3") (pintype "passive"))
      (node (ref "SV102") (pin "5") (pinfunction "5_5") (pintype "passive"))
      (node (ref "SV102") (pin "7") (pinfunction "7_7") (pintype "passive"))
      (node (ref "SV102") (pin "9") (pinfunction "9_9") (pintype "passive"))
    )
    (net (code "120") (name "~{TMS_IRQ}") (class "Default")
      (node (ref "IC101") (pin "5") (pinfunction "IN5_5") (pintype "input"))
      (node (ref "IC202") (pin "16") (pinfunction "~{INT}_16") (pintype "output"))
      (node (ref "LED201") (pin "C") (pinfunction "C_C") (pintype "passive"))
      (node (ref "R205") (pin "1") (pinfunction "1_1") (pintype "passive"))
    )
    (net (code "121") (name "~{TMS_RAS}") (class "Default")
      (node (ref "IC201") (pin "3") (pinfunction "I_3") (pintype "input"))
      (node (ref "IC202") (pin "1") (pinfunction "~{RAS}_1") (pintype "output"))
    )
    (net (code "122") (name "~{TMS_RD}") (class "Default")
      (node (ref "IC201") (pin "13") (pinfunction "I_13") (pintype "input"))
      (node (ref "IC201") (pin "2") (pinfunction "O_2") (pintype "output"))
      (node (ref "IC203") (pin "22") (pinfunction "~{OE}_22") (pintype "input"))
      (node (ref "IC204") (pin "11") (pinfunction "CLK_11") (pintype "input"))
    )
    (net (code "123") (name "~{TMS_RESET}") (class "Default")
      (node (ref "IC101") (pin "19") (pinfunction "IO19_19") (pintype "bidirectional"))
      (node (ref "IC202") (pin "34") (pinfunction "~{RESET}_34") (pintype "input"))
    )
    (net (code "124") (name "~{TMS_WR}") (class "Default")
      (node (ref "IC201") (pin "12") (pinfunction "O_12") (pintype "output"))
    )
  )
)
